# 26DC_20V_REBUILD.net
KiCad netlist of a schematic drawn in Altium Designer
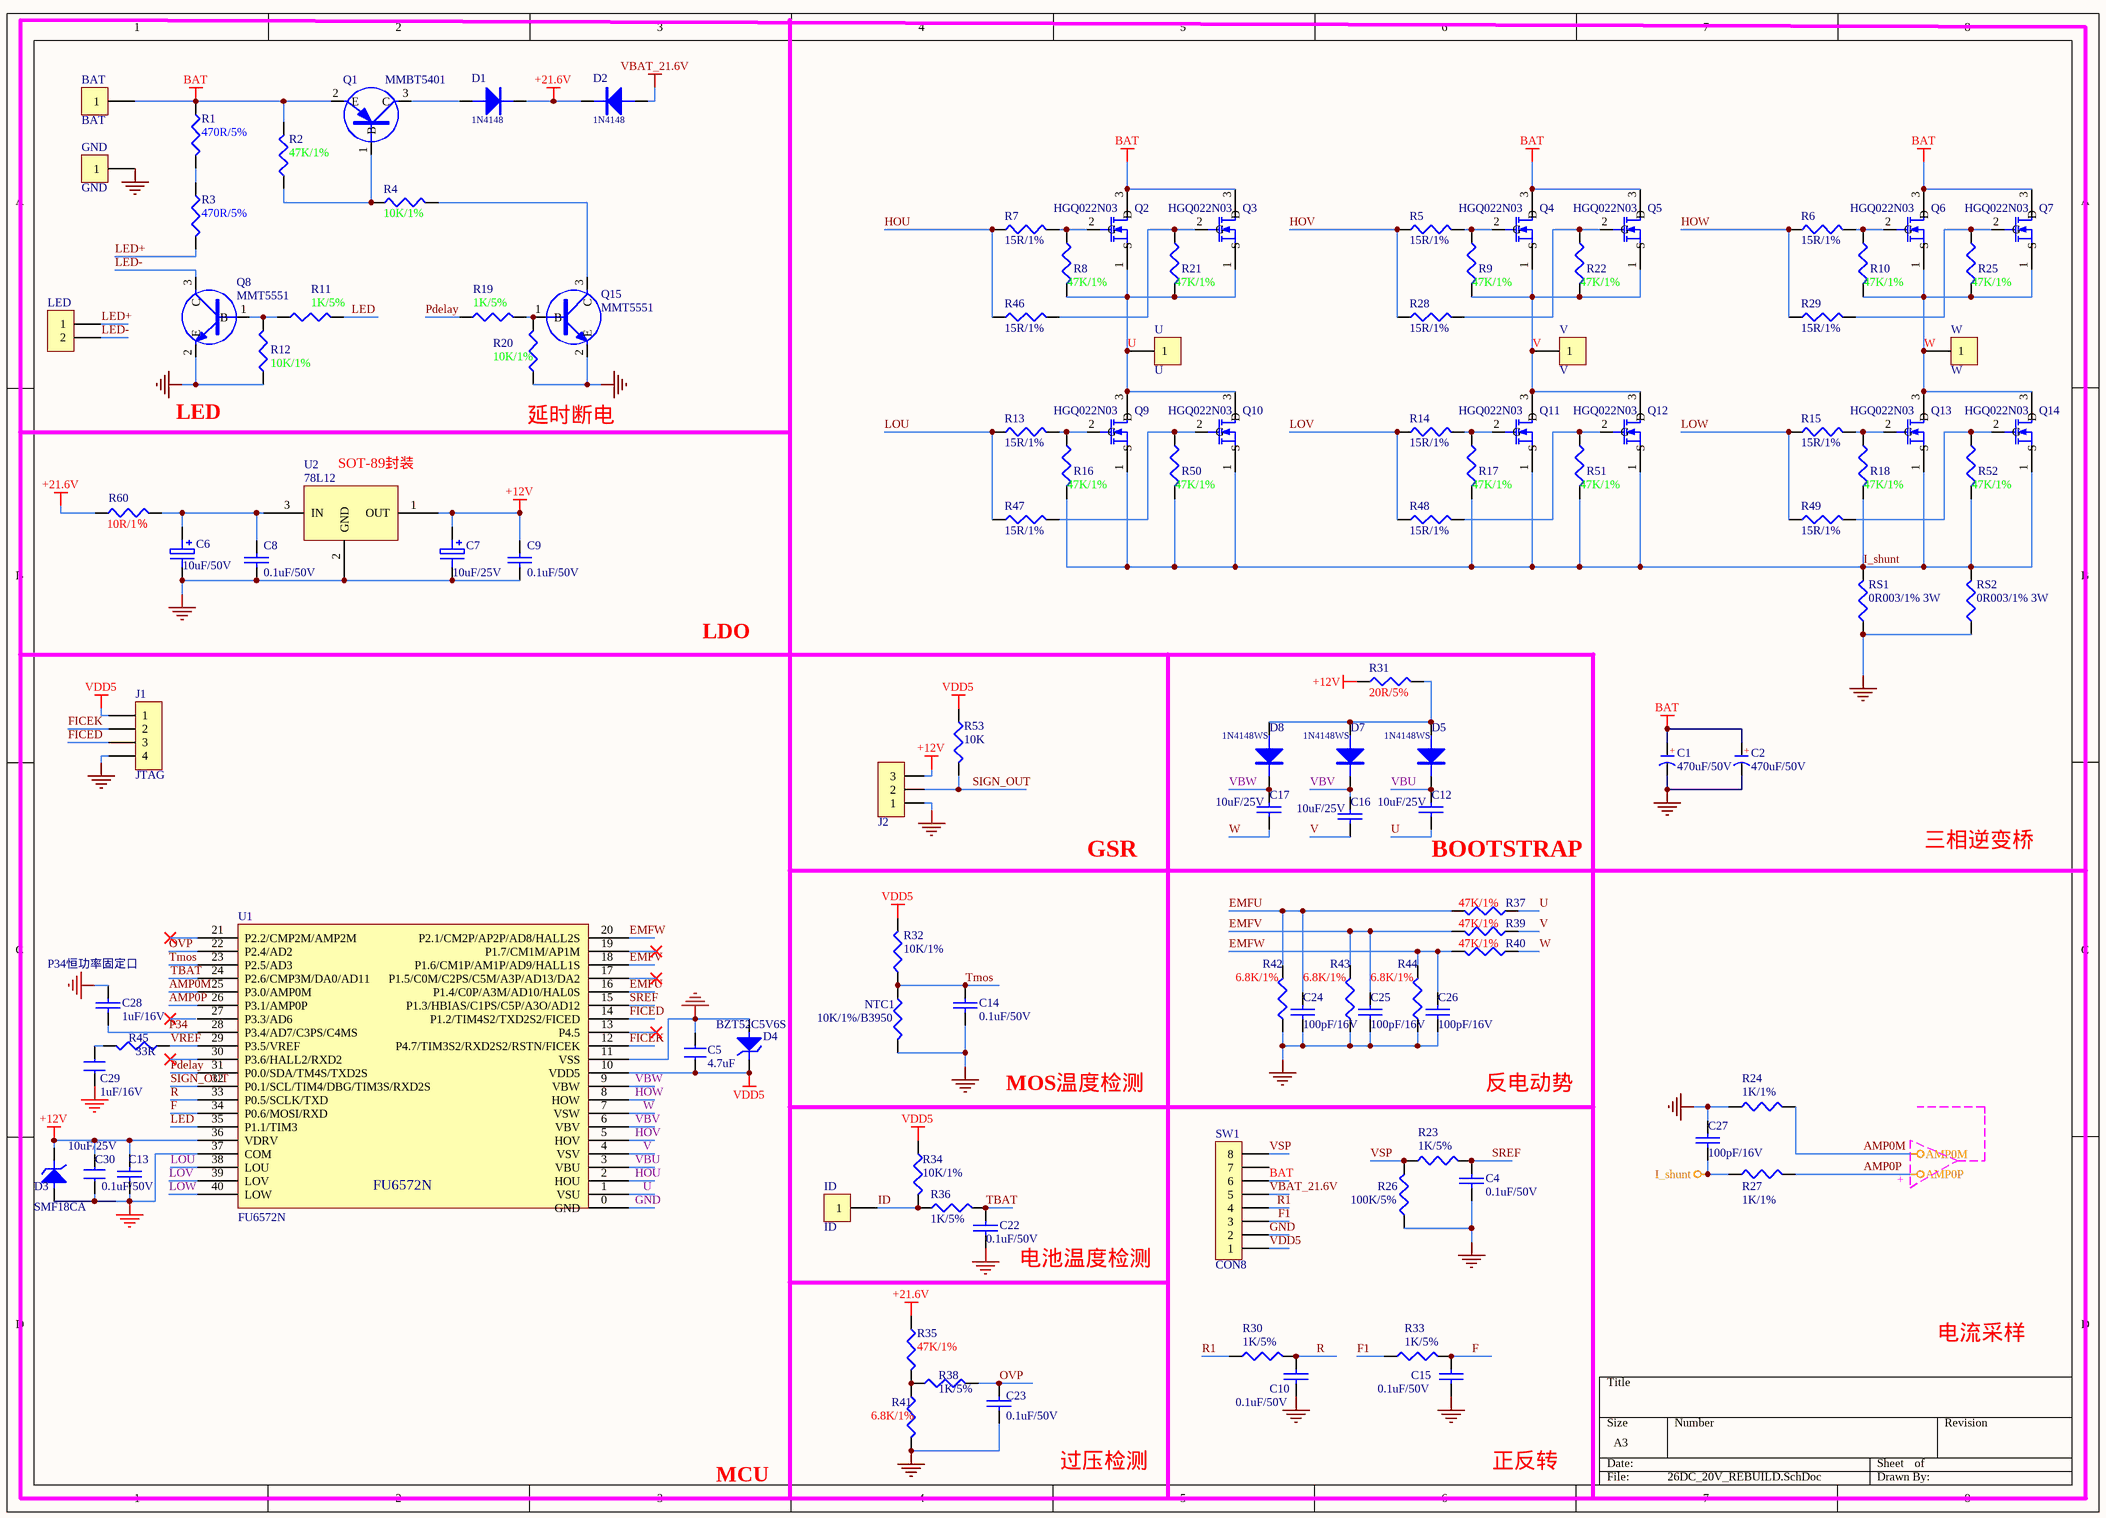
[diagram p0: 26DC_20V_REBUILD.SchDoc]

(export (version "E")
  (design (tool "Eeschema 10.0.6"))
  (components
    (comp (ref "BAT")
      (value "BAT")
      (footprint "TP")
      (description "Connector")
      (libsource (lib "26DC_20V_V1.3") (part "CON1_4"))
    )
    (comp (ref "C1")
      (value "470uF/50V")
      (footprint "CE-5.0*10*16 - GD")
      (description "直插电解电容")
      (libsource (lib "26DC_20V_V1.3") (part "CE"))
    )
    (comp (ref "C2")
      (value "470uF/50V")
      (footprint "CE-5.0*10*16 - GD")
      (description "直插电解电容")
      (libsource (lib "26DC_20V_V1.3") (part "CE"))
    )
    (comp (ref "C4")
      (value "0.1uF/50V")
      (footprint "C0603")
      (description "Capacitor")
      (libsource (lib "26DC_20V_V1.3") (part "CAP-CC"))
    )
    (comp (ref "C5")
      (value "4.7uF")
      (footprint "C0603")
      (description "Capacitor")
      (libsource (lib "") (part "CAP_1"))
    )
    (comp (ref "C6")
      (value "10uF/50V")
      (footprint "C0805")
      (description "Electrolytic Capacitor")
      (libsource (lib "26DC_20V_V1.3") (part "ELECTRO1"))
    )
    (comp (ref "C7")
      (value "10uF/25V")
      (footprint "C0805")
      (description "Electrolytic Capacitor")
      (libsource (lib "26DC_20V_V1.3") (part "ELECTRO1_1"))
    )
    (comp (ref "C8")
      (value "0.1uF/50V")
      (footprint "C0603")
      (description "Capacitor")
      (libsource (lib "26DC_20V_V1.3") (part "CAP"))
    )
    (comp (ref "C9")
      (value "0.1uF/50V")
      (footprint "C0603")
      (description "Capacitor")
      (libsource (lib "26DC_20V_V1.3") (part "CAP"))
    )
    (comp (ref "C10")
      (value "0.1uF/50V")
      (footprint "C0603")
      (description "Capacitor")
      (libsource (lib "26DC_20V_V1.3") (part "CAP-CC"))
    )
    (comp (ref "C12")
      (value "10uF/25V")
      (footprint "C0805")
      (description "Capacitor")
      (libsource (lib "*") (part "CAP-CC(SMD)"))
    )
    (comp (ref "C13")
      (value "0.1uF/50V")
      (footprint "C0603")
      (description "Capacitor")
      (libsource (lib "*") (part "CAP-CC"))
    )
    (comp (ref "C14")
      (value "0.1uF/50V")
      (footprint "C0603")
      (description "Capacitor")
      (libsource (lib "26DC_20V_V1.3") (part "CAP-CC"))
    )
    (comp (ref "C15")
      (value "0.1uF/50V")
      (footprint "C0603")
      (description "Capacitor")
      (libsource (lib "26DC_20V_V1.3") (part "CAP-CC"))
    )
    (comp (ref "C16")
      (value "10uF/25V")
      (footprint "C0805")
      (description "Capacitor")
      (libsource (lib "*") (part "CAP-CC(SMD)"))
    )
    (comp (ref "C17")
      (value "10uF/25V")
      (footprint "C0805")
      (description "Capacitor")
      (libsource (lib "*") (part "CAP-CC(SMD)"))
    )
    (comp (ref "C22")
      (value "0.1uF/50V")
      (footprint "C0603")
      (description "Capacitor")
      (libsource (lib "*") (part "CAP-CC"))
    )
    (comp (ref "C23")
      (value "0.1uF/50V")
      (footprint "C0603")
      (description "Capacitor")
      (libsource (lib "*") (part "CAP-CC"))
    )
    (comp (ref "C24")
      (value "100pF/16V")
      (footprint "C0603")
      (description "Capacitor")
      (libsource (lib "26DC_20V_V1.3") (part "CAP_1"))
    )
    (comp (ref "C25")
      (value "100pF/16V")
      (footprint "C0603")
      (description "Capacitor")
      (libsource (lib "26DC_20V_V1.3") (part "CAP_1"))
    )
    (comp (ref "C26")
      (value "100pF/16V")
      (footprint "C0603")
      (description "Capacitor")
      (libsource (lib "26DC_20V_V1.3") (part "CAP_1"))
    )
    (comp (ref "C27")
      (value "100pF/16V")
      (footprint "C0603")
      (description "Capacitor")
      (libsource (lib "26DC_20V_V1.3") (part "CAP_1"))
    )
    (comp (ref "C28")
      (value "1uF/16V")
      (footprint "C0603")
      (description "Capacitor")
      (libsource (lib "*") (part "CAP"))
    )
    (comp (ref "C29")
      (value "1uF/16V")
      (footprint "C0603")
      (description "Capacitor")
      (libsource (lib "") (part "CAP_1"))
    )
    (comp (ref "C30")
      (value "10uF/25V")
      (footprint "C0805")
      (description "Capacitor")
      (libsource (lib "") (part "CAP_1"))
    )
    (comp (ref "D1") (value "1N4148") (footprint "SOD-123") (libsource (lib "26DC_20V_V1.3") (part "DIODE")))
    (comp (ref "D2") (value "1N4148") (footprint "SOD-123") (libsource (lib "26DC_20V_V1.3") (part "DIODE")))
    (comp (ref "D3")
      (value "SMF18CA")
      (footprint "SOD-123")
      (description "Zener Diode")
      (libsource (lib "*") (part "TVS1"))
    )
    (comp (ref "D4")
      (value "BZT52C5V6S")
      (footprint "SOD-323")
      (description "Zener Diode")
      (libsource (lib "*") (part "TVS1"))
    )
    (comp (ref "D5")
      (value "1N4148WS")
      (footprint "SOD-323")
      (libsource (lib "FU6572N-HY-DC_V3.0") (part "DIODE"))
    )
    (comp (ref "D7")
      (value "1N4148WS")
      (footprint "SOD-323")
      (libsource (lib "FU6572N-HY-DC_V3.0") (part "DIODE"))
    )
    (comp (ref "D8")
      (value "1N4148WS")
      (footprint "SOD-323")
      (libsource (lib "FU6572N-HY-DC_V3.0") (part "DIODE"))
    )
    (comp (ref "GND")
      (value "GND")
      (footprint "TP")
      (description "Connector")
      (libsource (lib "26DC_20V_V1.3") (part "CON1_5"))
    )
    (comp (ref "ID")
      (value "ID")
      (footprint "TP")
      (description "Connector")
      (libsource (lib "*") (part "CON1"))
    )
    (comp (ref "J1")
      (value "JTAG")
      (footprint "4p-2.54-Pad")
      (description "Connector")
      (libsource (lib "26DC_20V_V1.3") (part "CON4"))
    )
    (comp (ref "J2")
      (value "HDR-1X3_1.25")
      (footprint "CONN-SMD-3P-P1.00_BM03B-SRSS-TB-LF-SN")
      (description "3P接插件_1.25")
      (libsource (lib "26DC_20V_V1.1") (part "Header 3_1.25"))
    )
    (comp (ref "LED")
      (value "CONN-SMD_2P-P1.00_HC-1.0-2PLT")
      (footprint "SMD_1.0_2P")
      (description "Connector")
      (libsource (lib "26DC_20V_V1.3") (part "CON2"))
    )
    (comp (ref "NTC1")
      (value "10K/1%/B3950")
      (footprint "R0603")
      (libsource (lib "26DC_20V_V1.3") (part "RES(SMD)_5"))
    )
    (comp (ref "Q1") (value "MMBT5401") (footprint "SOT-23") (libsource (lib "26DC_20V_V1.3") (part "PNP")))
    (comp (ref "Q2")
      (value "HGQ022N03")
      (footprint "DFN5*6")
      (libsource (lib "26DC_20V_V1.3") (part "HGQ022N03"))
    )
    (comp (ref "Q3")
      (value "HGQ022N03")
      (footprint "DFN5*6")
      (libsource (lib "26DC_20V_V1.3") (part "HGQ022N03"))
    )
    (comp (ref "Q4")
      (value "HGQ022N03")
      (footprint "DFN5*6")
      (libsource (lib "26DC_20V_V1.3") (part "HGQ022N03"))
    )
    (comp (ref "Q5")
      (value "HGQ022N03")
      (footprint "DFN5*6")
      (libsource (lib "26DC_20V_V1.3") (part "HGQ022N03"))
    )
    (comp (ref "Q6")
      (value "HGQ022N03")
      (footprint "DFN5*6")
      (libsource (lib "26DC_20V_V1.3") (part "HGQ022N03"))
    )
    (comp (ref "Q7")
      (value "HGQ022N03")
      (footprint "DFN5*6")
      (libsource (lib "26DC_20V_V1.3") (part "HGQ022N03"))
    )
    (comp (ref "Q8")
      (value "MMT5551")
      (footprint "SOT-23")
      (description "NPN Transistor")
      (libsource (lib "26DC_20V_V1.3") (part "NPN"))
    )
    (comp (ref "Q9")
      (value "HGQ022N03")
      (footprint "DFN5*6")
      (libsource (lib "26DC_20V_V1.3") (part "HGQ022N03"))
    )
    (comp (ref "Q10")
      (value "HGQ022N03")
      (footprint "DFN5*6")
      (libsource (lib "26DC_20V_V1.3") (part "HGQ022N03"))
    )
    (comp (ref "Q11")
      (value "HGQ022N03")
      (footprint "DFN5*6")
      (libsource (lib "26DC_20V_V1.3") (part "HGQ022N03"))
    )
    (comp (ref "Q12")
      (value "HGQ022N03")
      (footprint "DFN5*6")
      (libsource (lib "26DC_20V_V1.3") (part "HGQ022N03"))
    )
    (comp (ref "Q13")
      (value "HGQ022N03")
      (footprint "DFN5*6")
      (libsource (lib "26DC_20V_V1.3") (part "HGQ022N03"))
    )
    (comp (ref "Q14")
      (value "HGQ022N03")
      (footprint "DFN5*6")
      (libsource (lib "26DC_20V_V1.3") (part "HGQ022N03"))
    )
    (comp (ref "Q15")
      (value "MMT5551")
      (footprint "SOT-23")
      (description "NPN Transistor")
      (libsource (lib "26DC_20V_V1.3") (part "NPN"))
    )
    (comp (ref "R1")
      (value "470R/5%")
      (footprint "R1206")
      (libsource (lib "26DC_20V_V1.3") (part "RES(SMD)_4"))
    )
    (comp (ref "R2") (value "47K/1%") (footprint "R0603") (libsource (lib "26DC_20V_V1.3") (part "RES(SMD)")))
    (comp (ref "R3")
      (value "470R/5%")
      (footprint "R1206")
      (libsource (lib "26DC_20V_V1.3") (part "RES(SMD)_4"))
    )
    (comp (ref "R4")
      (value "10K/1%")
      (footprint "R0603")
      (libsource (lib "26DC_20V_V1.3") (part "RES(SMD)_3"))
    )
    (comp (ref "R5")
      (value "15R/1%")
      (footprint "R0603")
      (libsource (lib "26DC_20V_V1.3") (part "RES(SMD)_7"))
    )
    (comp (ref "R6")
      (value "15R/1%")
      (footprint "R0603")
      (libsource (lib "26DC_20V_V1.3") (part "RES(SMD)_7"))
    )
    (comp (ref "R7")
      (value "15R/1%")
      (footprint "R0603")
      (libsource (lib "26DC_20V_V1.3") (part "RES(SMD)_7"))
    )
    (comp (ref "R8")
      (value "47K/1%")
      (footprint "R0603")
      (description "RES")
      (libsource (lib "26DC_20V_V1.3") (part "RES-SMD"))
    )
    (comp (ref "R9")
      (value "47K/1%")
      (footprint "R0603")
      (description "RES")
      (libsource (lib "26DC_20V_V1.3") (part "RES-SMD"))
    )
    (comp (ref "R10")
      (value "47K/1%")
      (footprint "R0603")
      (description "RES")
      (libsource (lib "26DC_20V_V1.3") (part "RES-SMD"))
    )
    (comp (ref "R11")
      (value "1K/5%")
      (footprint "R0603")
      (libsource (lib "26DC_20V_V1.3") (part "RES(SMD)_2"))
    )
    (comp (ref "R12")
      (value "10K/1%")
      (footprint "R0603")
      (libsource (lib "26DC_20V_V1.3") (part "RES(SMD)_3"))
    )
    (comp (ref "R13")
      (value "15R/1%")
      (footprint "R0603")
      (libsource (lib "26DC_20V_V1.3") (part "RES(SMD)_7"))
    )
    (comp (ref "R14")
      (value "15R/1%")
      (footprint "R0603")
      (libsource (lib "26DC_20V_V1.3") (part "RES(SMD)_7"))
    )
    (comp (ref "R15")
      (value "15R/1%")
      (footprint "R0603")
      (libsource (lib "26DC_20V_V1.3") (part "RES(SMD)_7"))
    )
    (comp (ref "R16")
      (value "47K/1%")
      (footprint "R0603")
      (description "RES")
      (libsource (lib "26DC_20V_V1.3") (part "RES-SMD"))
    )
    (comp (ref "R17")
      (value "47K/1%")
      (footprint "R0603")
      (description "RES")
      (libsource (lib "26DC_20V_V1.3") (part "RES-SMD"))
    )
    (comp (ref "R18")
      (value "47K/1%")
      (footprint "R0603")
      (description "RES")
      (libsource (lib "26DC_20V_V1.3") (part "RES-SMD"))
    )
    (comp (ref "R19")
      (value "1K/5%")
      (footprint "R0603")
      (libsource (lib "26DC_20V_V1.3") (part "RES(SMD)_2"))
    )
    (comp (ref "R20")
      (value "10K/1%")
      (footprint "R0603")
      (libsource (lib "26DC_20V_V1.3") (part "RES(SMD)_3"))
    )
    (comp (ref "R21")
      (value "47K/1%")
      (footprint "R0603")
      (description "RES")
      (libsource (lib "26DC_20V_V1.3") (part "RES-SMD"))
    )
    (comp (ref "R22")
      (value "47K/1%")
      (footprint "R0603")
      (description "RES")
      (libsource (lib "26DC_20V_V1.3") (part "RES-SMD"))
    )
    (comp (ref "R23")
      (value "1K/5%")
      (footprint "R0603")
      (libsource (lib "26DC_20V_V1.3") (part "RES(SMD)_2"))
    )
    (comp (ref "R24")
      (value "1K/1%")
      (footprint "R0603")
      (libsource (lib "26DC_20V_V1.3") (part "RES(SMD)_11"))
    )
    (comp (ref "R25")
      (value "47K/1%")
      (footprint "R0603")
      (description "RES")
      (libsource (lib "26DC_20V_V1.3") (part "RES-SMD"))
    )
    (comp (ref "R26")
      (value "100K/5%")
      (footprint "R0603")
      (libsource (lib "26DC_20V_V1.3") (part "RES(SMD)_8"))
    )
    (comp (ref "R27")
      (value "1K/1%")
      (footprint "R0603")
      (libsource (lib "26DC_20V_V1.3") (part "RES(SMD)_11"))
    )
    (comp (ref "R28")
      (value "15R/1%")
      (footprint "R0603")
      (libsource (lib "26DC_20V_V1.3") (part "RES(SMD)_7"))
    )
    (comp (ref "R29")
      (value "15R/1%")
      (footprint "R0603")
      (libsource (lib "26DC_20V_V1.3") (part "RES(SMD)_7"))
    )
    (comp (ref "R30")
      (value "1K/5%")
      (footprint "R0603")
      (libsource (lib "26DC_20V_V1.3") (part "RES(SMD)_2"))
    )
    (comp (ref "R31") (value "20R/5%") (footprint "R1206") (libsource (lib "") (part "RES(SMD)_1")))
    (comp (ref "R32")
      (value "10K/1%")
      (footprint "R0603")
      (libsource (lib "26DC_20V_V1.3") (part "RES(SMD)_3"))
    )
    (comp (ref "R33")
      (value "1K/5%")
      (footprint "R0603")
      (libsource (lib "26DC_20V_V1.3") (part "RES(SMD)_2"))
    )
    (comp (ref "R34") (value "10K/1%") (footprint "R0603") (libsource (lib "*") (part "RES(SMD)")))
    (comp (ref "R35")
      (value "47K/1%")
      (footprint "R0603")
      (libsource (lib "26DC_20V_V1.3") (part "RES(SMD)"))
    )
    (comp (ref "R36") (value "1K/5%") (footprint "R0603") (libsource (lib "*") (part "RES(SMD)")))
    (comp (ref "R37")
      (value "47K/1%")
      (footprint "R0603")
      (libsource (lib "26DC_20V_V1.3") (part "RES(SMD)"))
    )
    (comp (ref "R38") (value "1K/5%") (footprint "R0603") (libsource (lib "*") (part "RES(SMD)")))
    (comp (ref "R39")
      (value "47K/1%")
      (footprint "R0603")
      (libsource (lib "26DC_20V_V1.3") (part "RES(SMD)"))
    )
    (comp (ref "R40")
      (value "47K/1%")
      (footprint "R0603")
      (libsource (lib "26DC_20V_V1.3") (part "RES(SMD)"))
    )
    (comp (ref "R41")
      (value "6.8K/1%")
      (footprint "R0603")
      (libsource (lib "26DC_20V_V1.3") (part "RES(SMD)"))
    )
    (comp (ref "R42")
      (value "6.8K/1%")
      (footprint "R0603")
      (libsource (lib "26DC_20V_V1.3") (part "RES(SMD)"))
    )
    (comp (ref "R43")
      (value "6.8K/1%")
      (footprint "R0603")
      (libsource (lib "26DC_20V_V1.3") (part "RES(SMD)"))
    )
    (comp (ref "R44")
      (value "6.8K/1%")
      (footprint "R0603")
      (libsource (lib "26DC_20V_V1.3") (part "RES(SMD)"))
    )
    (comp (ref "R45") (value "33R") (footprint "R0603") (libsource (lib "*") (part "RES(SMD)")))
    (comp (ref "R46")
      (value "15R/1%")
      (footprint "R0603")
      (libsource (lib "26DC_20V_V1.3") (part "RES(SMD)_7"))
    )
    (comp (ref "R47")
      (value "15R/1%")
      (footprint "R0603")
      (libsource (lib "26DC_20V_V1.3") (part "RES(SMD)_7"))
    )
    (comp (ref "R48")
      (value "15R/1%")
      (footprint "R0603")
      (libsource (lib "26DC_20V_V1.3") (part "RES(SMD)_7"))
    )
    (comp (ref "R49")
      (value "15R/1%")
      (footprint "R0603")
      (libsource (lib "26DC_20V_V1.3") (part "RES(SMD)_7"))
    )
    (comp (ref "R50")
      (value "47K/1%")
      (footprint "R0603")
      (description "RES")
      (libsource (lib "26DC_20V_V1.3") (part "RES-SMD"))
    )
    (comp (ref "R51")
      (value "47K/1%")
      (footprint "R0603")
      (description "RES")
      (libsource (lib "26DC_20V_V1.3") (part "RES-SMD"))
    )
    (comp (ref "R52")
      (value "47K/1%")
      (footprint "R0603")
      (description "RES")
      (libsource (lib "26DC_20V_V1.3") (part "RES-SMD"))
    )
    (comp (ref "R53") (value "10K") (footprint "R0603") (libsource (lib "*") (part "RES(SMD)")))
    (comp (ref "R60")
      (value "10R/1％")
      (footprint "R1206")
      (libsource (lib "26DC_20V_V1.3") (part "RES(SMD)_9"))
    )
    (comp (ref "RS1")
      (value "0R003/1% 3W")
      (footprint "R2512")
      (libsource (lib "26DC_20V_V1.3") (part "RES(SMD)_6"))
    )
    (comp (ref "RS2")
      (value "0R003/1% 3W")
      (footprint "R2512")
      (libsource (lib "26DC_20V_V1.3") (part "RES(SMD)_6"))
    )
    (comp (ref "SW1")
      (value "CON8")
      (footprint "CONN-SMD_8P-P1.00_MEGASTAR_ZX-SH1.0-8PLT")
      (description "Connector")
      (libsource (lib "26DC_20V_V1.3") (part "CON6"))
    )
    (comp (ref "U")
      (value "U")
      (footprint "TP")
      (description "Connector")
      (libsource (lib "26DC_20V_V1.3") (part "CON1"))
    )
    (comp (ref "U1") (value "FU6572N") (footprint "QFN40_5*5") (libsource (lib "SCH 常用封装") (part "FU6572N")))
    (comp (ref "U2")
      (value "78L12")
      (footprint "SOT-89")
      (libsource (lib "26DC_20V_V1.3") (part "78L12-12V"))
    )
    (comp (ref "V")
      (value "V")
      (footprint "TP")
      (description "Connector")
      (libsource (lib "26DC_20V_V1.3") (part "CON1"))
    )
    (comp (ref "W")
      (value "W")
      (footprint "TP")
      (description "Connector")
      (libsource (lib "26DC_20V_V1.3") (part "CON1"))
    )
  )
  (nets
    (net (code "1") (name "+12V") (class "Default")
      (node (ref "C13") (pin "1") (pinfunction "1_1") (pintype "passive"))
      (node (ref "C30") (pin "2") (pinfunction "2_2") (pintype "passive"))
      (node (ref "C7") (pin "1") (pinfunction "1_1") (pintype "passive"))
      (node (ref "C9") (pin "1") (pinfunction "1_1") (pintype "passive"))
      (node (ref "D3") (pin "2") (pinfunction "K_2") (pintype "passive"))
      (node (ref "J2") (pin "3") (pinfunction "3_3") (pintype "passive"))
      (node (ref "R31") (pin "1") (pinfunction "1_1") (pintype "passive"))
      (node (ref "U1") (pin "36") (pinfunction "VDRV_36") (pintype "passive"))
      (node (ref "U2") (pin "1") (pinfunction "OUT_1") (pintype "passive"))
    )
    (net (code "2") (name "+21.6V") (class "Default")
      (node (ref "D1") (pin "K") (pinfunction "K_K") (pintype "passive"))
      (node (ref "D2") (pin "K") (pinfunction "K_K") (pintype "passive"))
      (node (ref "R35") (pin "1") (pinfunction "1_1") (pintype "passive"))
      (node (ref "R60") (pin "1") (pinfunction "1_1") (pintype "passive"))
    )
    (net (code "3") (name "/EMFU") (class "Default")
      (node (ref "C24") (pin "2") (pinfunction "2_2") (pintype "passive"))
      (node (ref "R37") (pin "2") (pinfunction "2_2") (pintype "passive"))
      (node (ref "R42") (pin "2") (pinfunction "2_2") (pintype "passive"))
      (node (ref "U1") (pin "16") (pinfunction "P1.4/C0P/A3M/AD10/HAL0S_16") (pintype "passive"))
    )
    (net (code "4") (name "/EMFV") (class "Default")
      (node (ref "C25") (pin "2") (pinfunction "2_2") (pintype "passive"))
      (node (ref "R39") (pin "2") (pinfunction "2_2") (pintype "passive"))
      (node (ref "R43") (pin "2") (pinfunction "2_2") (pintype "passive"))
      (node (ref "U1") (pin "18") (pinfunction "P1.6/CM1P/AM1P/AD9/HALL1S_18") (pintype "passive"))
    )
    (net (code "5") (name "/EMFW") (class "Default")
      (node (ref "C26") (pin "2") (pinfunction "2_2") (pintype "passive"))
      (node (ref "R40") (pin "2") (pinfunction "2_2") (pintype "passive"))
      (node (ref "R44") (pin "2") (pinfunction "2_2") (pintype "passive"))
      (node (ref "U1") (pin "20") (pinfunction "P2.1/CM2P/AP2P/AD8/HALL2S_20") (pintype "passive"))
    )
    (net (code "6") (name "/F") (class "Default")
      (node (ref "C15") (pin "1") (pinfunction "1_1") (pintype "passive"))
      (node (ref "R33") (pin "2") (pinfunction "2_2") (pintype "passive"))
      (node (ref "U1") (pin "34") (pinfunction "P0.6/MOSI/RXD_34") (pintype "passive"))
    )
    (net (code "7") (name "/F1") (class "Default")
      (node (ref "R33") (pin "1") (pinfunction "1_1") (pintype "passive"))
      (node (ref "SW1") (pin "3") (pinfunction "3_3") (pintype "passive"))
    )
    (net (code "8") (name "/FICED") (class "Default")
      (node (ref "J1") (pin "3") (pinfunction "3_3") (pintype "passive"))
      (node (ref "U1") (pin "14") (pinfunction "P1.2/TIM4S2/TXD2S2/FICED_14") (pintype "passive"))
    )
    (net (code "9") (name "/FICEK") (class "Default")
      (node (ref "J1") (pin "2") (pinfunction "2_2") (pintype "passive"))
      (node (ref "U1") (pin "12") (pinfunction "P4.7/TIM3S2/RXD2S2/RSTN/FICEK_12") (pintype "passive"))
    )
    (net (code "10") (name "/HOU") (class "Default")
      (node (ref "R46") (pin "1") (pinfunction "1_1") (pintype "passive"))
      (node (ref "R7") (pin "1") (pinfunction "1_1") (pintype "passive"))
      (node (ref "U1") (pin "2") (pinfunction "HOU_2") (pintype "passive"))
    )
    (net (code "11") (name "/HOV") (class "Default")
      (node (ref "R28") (pin "1") (pinfunction "1_1") (pintype "passive"))
      (node (ref "R5") (pin "1") (pinfunction "1_1") (pintype "passive"))
      (node (ref "U1") (pin "5") (pinfunction "HOV_5") (pintype "passive"))
    )
    (net (code "12") (name "/HOW") (class "Default")
      (node (ref "R29") (pin "1") (pinfunction "1_1") (pintype "passive"))
      (node (ref "R6") (pin "1") (pinfunction "1_1") (pintype "passive"))
      (node (ref "U1") (pin "8") (pinfunction "HOW_8") (pintype "passive"))
    )
    (net (code "13") (name "/ID") (class "Default")
      (node (ref "ID") (pin "1") (pinfunction "1_1") (pintype "passive"))
      (node (ref "R34") (pin "2") (pinfunction "2_2") (pintype "passive"))
      (node (ref "R36") (pin "1") (pinfunction "1_1") (pintype "passive"))
    )
    (net (code "14") (name "/LED") (class "Default")
      (node (ref "R11") (pin "2") (pinfunction "2_2") (pintype "passive"))
      (node (ref "U1") (pin "35") (pinfunction "P1.1/TIM3_35") (pintype "passive"))
    )
    (net (code "15") (name "/LED+") (class "Default")
      (node (ref "LED") (pin "1") (pinfunction "1_1") (pintype "passive"))
      (node (ref "R3") (pin "2") (pinfunction "2_2") (pintype "passive"))
    )
    (net (code "16") (name "/LED-") (class "Default")
      (node (ref "LED") (pin "2") (pinfunction "2_2") (pintype "passive"))
      (node (ref "Q8") (pin "3") (pinfunction "C_3") (pintype "passive"))
    )
    (net (code "17") (name "/LOU") (class "Default")
      (node (ref "R13") (pin "1") (pinfunction "1_1") (pintype "passive"))
      (node (ref "R47") (pin "1") (pinfunction "1_1") (pintype "passive"))
      (node (ref "U1") (pin "38") (pinfunction "LOU_38") (pintype "passive"))
    )
    (net (code "18") (name "/LOV") (class "Default")
      (node (ref "R14") (pin "1") (pinfunction "1_1") (pintype "passive"))
      (node (ref "R48") (pin "1") (pinfunction "1_1") (pintype "passive"))
      (node (ref "U1") (pin "39") (pinfunction "LOV_39") (pintype "passive"))
    )
    (net (code "19") (name "/LOW") (class "Default")
      (node (ref "R15") (pin "1") (pinfunction "1_1") (pintype "passive"))
      (node (ref "R49") (pin "1") (pinfunction "1_1") (pintype "passive"))
      (node (ref "U1") (pin "40") (pinfunction "LOW_40") (pintype "passive"))
    )
    (net (code "20") (name "/OVP") (class "Default")
      (node (ref "C23") (pin "1") (pinfunction "1_1") (pintype "passive"))
      (node (ref "R38") (pin "2") (pinfunction "2_2") (pintype "passive"))
      (node (ref "U1") (pin "22") (pinfunction "P2.4/AD2_22") (pintype "passive"))
    )
    (net (code "21") (name "/P34") (class "Default")
      (node (ref "C28") (pin "1") (pinfunction "1_1") (pintype "passive"))
      (node (ref "U1") (pin "28") (pinfunction "P3.4/AD7/C3PS/C4MS_28") (pintype "passive"))
    )
    (net (code "22") (name "/Pdelay") (class "Default")
      (node (ref "R19") (pin "1") (pinfunction "1_1") (pintype "passive"))
      (node (ref "U1") (pin "31") (pinfunction "P0.0/SDA/TM4S/TXD2S_31") (pintype "passive"))
    )
    (net (code "23") (name "/R") (class "Default")
      (node (ref "C10") (pin "1") (pinfunction "1_1") (pintype "passive"))
      (node (ref "R30") (pin "2") (pinfunction "2_2") (pintype "passive"))
      (node (ref "U1") (pin "33") (pinfunction "P0.5/SCLK/TXD_33") (pintype "passive"))
    )
    (net (code "24") (name "/R1") (class "Default")
      (node (ref "R30") (pin "1") (pinfunction "1_1") (pintype "passive"))
      (node (ref "SW1") (pin "4") (pinfunction "4_4") (pintype "passive"))
    )
    (net (code "25") (name "/SIGN_OUT") (class "Default")
      (node (ref "J2") (pin "2") (pinfunction "2_2") (pintype "passive"))
      (node (ref "R53") (pin "2") (pinfunction "2_2") (pintype "passive"))
      (node (ref "U1") (pin "32") (pinfunction "P0.1/SCL/TIM4/DBG/TIM3S/RXD2S_32") (pintype "passive"))
    )
    (net (code "26") (name "/SREF") (class "Default")
      (node (ref "C4") (pin "1") (pinfunction "1_1") (pintype "passive"))
      (node (ref "R23") (pin "2") (pinfunction "2_2") (pintype "passive"))
      (node (ref "U1") (pin "15") (pinfunction "P1.3/HBIAS/C1PS/C5P/A3O/AD12_15") (pintype "passive"))
    )
    (net (code "27") (name "/TBAT") (class "Default")
      (node (ref "C22") (pin "1") (pinfunction "1_1") (pintype "passive"))
      (node (ref "R36") (pin "2") (pinfunction "2_2") (pintype "passive"))
      (node (ref "U1") (pin "24") (pinfunction "P2.6/CMP3M/DA0/AD11_24") (pintype "passive"))
    )
    (net (code "28") (name "/Tmos") (class "Default")
      (node (ref "C14") (pin "1") (pinfunction "1_1") (pintype "passive"))
      (node (ref "NTC1") (pin "1") (pinfunction "1_1") (pintype "passive"))
      (node (ref "R32") (pin "1") (pinfunction "1_1") (pintype "passive"))
      (node (ref "U1") (pin "23") (pinfunction "P2.5/AD3_23") (pintype "passive"))
    )
    (net (code "29") (name "/U") (class "Default")
      (node (ref "C12") (pin "2") (pinfunction "2_2") (pintype "passive"))
      (node (ref "Q10") (pin "3") (pinfunction "D_3") (pintype "passive"))
      (node (ref "Q2") (pin "1") (pinfunction "S_1") (pintype "passive"))
      (node (ref "Q3") (pin "1") (pinfunction "S_1") (pintype "passive"))
      (node (ref "Q9") (pin "3") (pinfunction "D_3") (pintype "passive"))
      (node (ref "R21") (pin "2") (pinfunction "2_2") (pintype "passive"))
      (node (ref "R37") (pin "1") (pinfunction "1_1") (pintype "passive"))
      (node (ref "R8") (pin "2") (pinfunction "2_2") (pintype "passive"))
      (node (ref "U") (pin "1") (pinfunction "1_1") (pintype "passive"))
      (node (ref "U1") (pin "1") (pinfunction "VSU_1") (pintype "passive"))
    )
    (net (code "30") (name "/V") (class "Default")
      (node (ref "C16") (pin "1") (pinfunction "1_1") (pintype "passive"))
      (node (ref "Q11") (pin "3") (pinfunction "D_3") (pintype "passive"))
      (node (ref "Q12") (pin "3") (pinfunction "D_3") (pintype "passive"))
      (node (ref "Q4") (pin "1") (pinfunction "S_1") (pintype "passive"))
      (node (ref "Q5") (pin "1") (pinfunction "S_1") (pintype "passive"))
      (node (ref "R22") (pin "2") (pinfunction "2_2") (pintype "passive"))
      (node (ref "R39") (pin "1") (pinfunction "1_1") (pintype "passive"))
      (node (ref "R9") (pin "2") (pinfunction "2_2") (pintype "passive"))
      (node (ref "U1") (pin "4") (pinfunction "VSV_4") (pintype "passive"))
      (node (ref "V") (pin "1") (pinfunction "1_1") (pintype "passive"))
    )
    (net (code "31") (name "/VBU") (class "Default")
      (node (ref "C12") (pin "1") (pinfunction "1_1") (pintype "passive"))
      (node (ref "D5") (pin "K") (pinfunction "K_K") (pintype "passive"))
      (node (ref "U1") (pin "3") (pinfunction "VBU_3") (pintype "passive"))
    )
    (net (code "32") (name "/VBV") (class "Default")
      (node (ref "C16") (pin "2") (pinfunction "2_2") (pintype "passive"))
      (node (ref "D7") (pin "K") (pinfunction "K_K") (pintype "passive"))
      (node (ref "U1") (pin "6") (pinfunction "VBV_6") (pintype "passive"))
    )
    (net (code "33") (name "/VBW") (class "Default")
      (node (ref "C17") (pin "1") (pinfunction "1_1") (pintype "passive"))
      (node (ref "D8") (pin "K") (pinfunction "K_K") (pintype "passive"))
      (node (ref "U1") (pin "9") (pinfunction "VBW_9") (pintype "passive"))
    )
    (net (code "34") (name "/VREF") (class "Default")
      (node (ref "R45") (pin "1") (pinfunction "1_1") (pintype "passive"))
      (node (ref "U1") (pin "29") (pinfunction "P3.5/VREF_29") (pintype "passive"))
    )
    (net (code "35") (name "/VSP") (class "Default")
      (node (ref "R23") (pin "1") (pinfunction "1_1") (pintype "passive"))
      (node (ref "R26") (pin "2") (pinfunction "2_2") (pintype "passive"))
      (node (ref "SW1") (pin "8") (pinfunction "8_8") (pintype "passive"))
    )
    (net (code "36") (name "/W") (class "Default")
      (node (ref "C17") (pin "2") (pinfunction "2_2") (pintype "passive"))
      (node (ref "Q13") (pin "3") (pinfunction "D_3") (pintype "passive"))
      (node (ref "Q14") (pin "3") (pinfunction "D_3") (pintype "passive"))
      (node (ref "Q6") (pin "1") (pinfunction "S_1") (pintype "passive"))
      (node (ref "Q7") (pin "1") (pinfunction "S_1") (pintype "passive"))
      (node (ref "R10") (pin "2") (pinfunction "2_2") (pintype "passive"))
      (node (ref "R25") (pin "2") (pinfunction "2_2") (pintype "passive"))
      (node (ref "R40") (pin "1") (pinfunction "1_1") (pintype "passive"))
      (node (ref "U1") (pin "7") (pinfunction "VSW_7") (pintype "passive"))
      (node (ref "W") (pin "1") (pinfunction "1_1") (pintype "passive"))
    )
    (net (code "37") (name "AMP0M") (class "Default")
      (node (ref "R24") (pin "2") (pinfunction "2_2") (pintype "passive"))
      (node (ref "U1") (pin "25") (pinfunction "P3.0/AMP0M_25") (pintype "passive"))
    )
    (net (code "38") (name "AMP0P") (class "Default")
      (node (ref "R27") (pin "2") (pinfunction "2_2") (pintype "passive"))
      (node (ref "U1") (pin "26") (pinfunction "P3.1/AMP0P_26") (pintype "passive"))
    )
    (net (code "39") (name "BAT") (class "Default")
      (node (ref "BAT") (pin "1") (pinfunction "1_1") (pintype "passive"))
      (node (ref "C1") (pin "1") (pinfunction "A_1") (pintype "passive"))
      (node (ref "C2") (pin "1") (pinfunction "A_1") (pintype "passive"))
      (node (ref "Q1") (pin "2") (pinfunction "E_2") (pintype "passive"))
      (node (ref "Q2") (pin "3") (pinfunction "D_3") (pintype "passive"))
      (node (ref "Q3") (pin "3") (pinfunction "D_3") (pintype "passive"))
      (node (ref "Q4") (pin "3") (pinfunction "D_3") (pintype "passive"))
      (node (ref "Q5") (pin "3") (pinfunction "D_3") (pintype "passive"))
      (node (ref "Q6") (pin "3") (pinfunction "D_3") (pintype "passive"))
      (node (ref "Q7") (pin "3") (pinfunction "D_3") (pintype "passive"))
      (node (ref "R1") (pin "1") (pinfunction "1_1") (pintype "passive"))
      (node (ref "R2") (pin "2") (pinfunction "2_2") (pintype "passive"))
      (node (ref "SW1") (pin "6") (pinfunction "6_6") (pintype "passive"))
    )
    (net (code "40") (name "GND") (class "Default")
      (node (ref "C1") (pin "2") (pinfunction "K_2") (pintype "passive"))
      (node (ref "C10") (pin "2") (pinfunction "2_2") (pintype "passive"))
      (node (ref "C13") (pin "2") (pinfunction "2_2") (pintype "passive"))
      (node (ref "C14") (pin "2") (pinfunction "2_2") (pintype "passive"))
      (node (ref "C15") (pin "2") (pinfunction "2_2") (pintype "passive"))
      (node (ref "C2") (pin "2") (pinfunction "K_2") (pintype "passive"))
      (node (ref "C22") (pin "2") (pinfunction "2_2") (pintype "passive"))
      (node (ref "C23") (pin "2") (pinfunction "2_2") (pintype "passive"))
      (node (ref "C24") (pin "1") (pinfunction "1_1") (pintype "passive"))
      (node (ref "C25") (pin "1") (pinfunction "1_1") (pintype "passive"))
      (node (ref "C26") (pin "1") (pinfunction "1_1") (pintype "passive"))
      (node (ref "C27") (pin "1") (pinfunction "1_1") (pintype "passive"))
      (node (ref "C28") (pin "2") (pinfunction "2_2") (pintype "passive"))
      (node (ref "C29") (pin "1") (pinfunction "1_1") (pintype "passive"))
      (node (ref "C30") (pin "1") (pinfunction "1_1") (pintype "passive"))
      (node (ref "C4") (pin "2") (pinfunction "2_2") (pintype "passive"))
      (node (ref "C5") (pin "2") (pinfunction "2_2") (pintype "passive"))
      (node (ref "C6") (pin "2") (pinfunction "2_2") (pintype "passive"))
      (node (ref "C7") (pin "2") (pinfunction "2_2") (pintype "passive"))
      (node (ref "C8") (pin "2") (pinfunction "2_2") (pintype "passive"))
      (node (ref "C9") (pin "2") (pinfunction "2_2") (pintype "passive"))
      (node (ref "D3") (pin "1") (pinfunction "A_1") (pintype "passive"))
      (node (ref "D4") (pin "1") (pinfunction "A_1") (pintype "passive"))
      (node (ref "GND") (pin "1") (pinfunction "1_1") (pintype "passive"))
      (node (ref "J1") (pin "4") (pinfunction "4_4") (pintype "passive"))
      (node (ref "J2") (pin "1") (pinfunction "1_1") (pintype "passive"))
      (node (ref "NTC1") (pin "2") (pinfunction "2_2") (pintype "passive"))
      (node (ref "Q15") (pin "2") (pinfunction "E_2") (pintype "passive"))
      (node (ref "Q8") (pin "2") (pinfunction "E_2") (pintype "passive"))
      (node (ref "R12") (pin "1") (pinfunction "1_1") (pintype "passive"))
      (node (ref "R20") (pin "1") (pinfunction "1_1") (pintype "passive"))
      (node (ref "R24") (pin "1") (pinfunction "1_1") (pintype "passive"))
      (node (ref "R26") (pin "1") (pinfunction "1_1") (pintype "passive"))
      (node (ref "R41") (pin "2") (pinfunction "2_2") (pintype "passive"))
      (node (ref "R42") (pin "1") (pinfunction "1_1") (pintype "passive"))
      (node (ref "R43") (pin "1") (pinfunction "1_1") (pintype "passive"))
      (node (ref "R44") (pin "1") (pinfunction "1_1") (pintype "passive"))
      (node (ref "RS1") (pin "1") (pinfunction "1_1") (pintype "passive"))
      (node (ref "RS2") (pin "1") (pinfunction "1_1") (pintype "passive"))
      (node (ref "SW1") (pin "2") (pinfunction "2_2") (pintype "passive"))
      (node (ref "U1") (pin "0") (pinfunction "GND_0") (pintype "passive"))
      (node (ref "U1") (pin "11") (pinfunction "VSS_11") (pintype "passive"))
      (node (ref "U1") (pin "37") (pinfunction "COM_37") (pintype "passive"))
      (node (ref "U2") (pin "2") (pinfunction "GND_2") (pintype "passive"))
    )
    (net (code "41") (name "I_shunt") (class "Default")
      (node (ref "C27") (pin "2") (pinfunction "2_2") (pintype "passive"))
      (node (ref "Q10") (pin "1") (pinfunction "S_1") (pintype "passive"))
      (node (ref "Q11") (pin "1") (pinfunction "S_1") (pintype "passive"))
      (node (ref "Q12") (pin "1") (pinfunction "S_1") (pintype "passive"))
      (node (ref "Q13") (pin "1") (pinfunction "S_1") (pintype "passive"))
      (node (ref "Q14") (pin "1") (pinfunction "S_1") (pintype "passive"))
      (node (ref "Q9") (pin "1") (pinfunction "S_1") (pintype "passive"))
      (node (ref "R16") (pin "2") (pinfunction "2_2") (pintype "passive"))
      (node (ref "R17") (pin "2") (pinfunction "2_2") (pintype "passive"))
      (node (ref "R18") (pin "2") (pinfunction "2_2") (pintype "passive"))
      (node (ref "R27") (pin "1") (pinfunction "1_1") (pintype "passive"))
      (node (ref "R50") (pin "2") (pinfunction "2_2") (pintype "passive"))
      (node (ref "R51") (pin "2") (pinfunction "2_2") (pintype "passive"))
      (node (ref "R52") (pin "2") (pinfunction "2_2") (pintype "passive"))
      (node (ref "RS1") (pin "2") (pinfunction "2_2") (pintype "passive"))
      (node (ref "RS2") (pin "2") (pinfunction "2_2") (pintype "passive"))
    )
    (net (code "42") (name "Net-(C29-Pad2)") (class "Default")
      (node (ref "C29") (pin "2") (pinfunction "2_2") (pintype "passive"))
      (node (ref "R45") (pin "2") (pinfunction "2_2") (pintype "passive"))
    )
    (net (code "43") (name "Net-(D5-PadA)") (class "Default")
      (node (ref "D5") (pin "A") (pinfunction "A_A") (pintype "passive"))
      (node (ref "D7") (pin "A") (pinfunction "A_A") (pintype "passive"))
      (node (ref "D8") (pin "A") (pinfunction "A_A") (pintype "passive"))
      (node (ref "R31") (pin "2") (pinfunction "2_2") (pintype "passive"))
    )
    (net (code "44") (name "Net-(Q1-B)") (class "Default")
      (node (ref "Q1") (pin "1") (pinfunction "B_1") (pintype "passive"))
      (node (ref "R2") (pin "1") (pinfunction "1_1") (pintype "passive"))
      (node (ref "R4") (pin "1") (pinfunction "1_1") (pintype "passive"))
    )
    (net (code "45") (name "Net-(Q1-C)") (class "Default")
      (node (ref "D1") (pin "A") (pinfunction "A_A") (pintype "passive"))
      (node (ref "Q1") (pin "3") (pinfunction "C_3") (pintype "passive"))
    )
    (net (code "46") (name "Net-(Q2-G)") (class "Default")
      (node (ref "Q2") (pin "2") (pinfunction "G_2") (pintype "passive"))
      (node (ref "R7") (pin "2") (pinfunction "2_2") (pintype "passive"))
      (node (ref "R8") (pin "1") (pinfunction "1_1") (pintype "passive"))
    )
    (net (code "47") (name "Net-(Q3-G)") (class "Default")
      (node (ref "Q3") (pin "2") (pinfunction "G_2") (pintype "passive"))
      (node (ref "R21") (pin "1") (pinfunction "1_1") (pintype "passive"))
      (node (ref "R46") (pin "2") (pinfunction "2_2") (pintype "passive"))
    )
    (net (code "48") (name "Net-(Q4-G)") (class "Default")
      (node (ref "Q4") (pin "2") (pinfunction "G_2") (pintype "passive"))
      (node (ref "R5") (pin "2") (pinfunction "2_2") (pintype "passive"))
      (node (ref "R9") (pin "1") (pinfunction "1_1") (pintype "passive"))
    )
    (net (code "49") (name "Net-(Q5-G)") (class "Default")
      (node (ref "Q5") (pin "2") (pinfunction "G_2") (pintype "passive"))
      (node (ref "R22") (pin "1") (pinfunction "1_1") (pintype "passive"))
      (node (ref "R28") (pin "2") (pinfunction "2_2") (pintype "passive"))
    )
    (net (code "50") (name "Net-(Q6-G)") (class "Default")
      (node (ref "Q6") (pin "2") (pinfunction "G_2") (pintype "passive"))
      (node (ref "R10") (pin "1") (pinfunction "1_1") (pintype "passive"))
      (node (ref "R6") (pin "2") (pinfunction "2_2") (pintype "passive"))
    )
    (net (code "51") (name "Net-(Q7-G)") (class "Default")
      (node (ref "Q7") (pin "2") (pinfunction "G_2") (pintype "passive"))
      (node (ref "R25") (pin "1") (pinfunction "1_1") (pintype "passive"))
      (node (ref "R29") (pin "2") (pinfunction "2_2") (pintype "passive"))
    )
    (net (code "52") (name "Net-(Q8-B)") (class "Default")
      (node (ref "Q8") (pin "1") (pinfunction "B_1") (pintype "passive"))
      (node (ref "R11") (pin "1") (pinfunction "1_1") (pintype "passive"))
      (node (ref "R12") (pin "2") (pinfunction "2_2") (pintype "passive"))
    )
    (net (code "53") (name "Net-(Q9-G)") (class "Default")
      (node (ref "Q9") (pin "2") (pinfunction "G_2") (pintype "passive"))
      (node (ref "R13") (pin "2") (pinfunction "2_2") (pintype "passive"))
      (node (ref "R16") (pin "1") (pinfunction "1_1") (pintype "passive"))
    )
    (net (code "54") (name "Net-(Q10-G)") (class "Default")
      (node (ref "Q10") (pin "2") (pinfunction "G_2") (pintype "passive"))
      (node (ref "R47") (pin "2") (pinfunction "2_2") (pintype "passive"))
      (node (ref "R50") (pin "1") (pinfunction "1_1") (pintype "passive"))
    )
    (net (code "55") (name "Net-(Q11-G)") (class "Default")
      (node (ref "Q11") (pin "2") (pinfunction "G_2") (pintype "passive"))
      (node (ref "R14") (pin "2") (pinfunction "2_2") (pintype "passive"))
      (node (ref "R17") (pin "1") (pinfunction "1_1") (pintype "passive"))
    )
    (net (code "56") (name "Net-(Q12-G)") (class "Default")
      (node (ref "Q12") (pin "2") (pinfunction "G_2") (pintype "passive"))
      (node (ref "R48") (pin "2") (pinfunction "2_2") (pintype "passive"))
      (node (ref "R51") (pin "1") (pinfunction "1_1") (pintype "passive"))
    )
    (net (code "57") (name "Net-(Q13-G)") (class "Default")
      (node (ref "Q13") (pin "2") (pinfunction "G_2") (pintype "passive"))
      (node (ref "R15") (pin "2") (pinfunction "2_2") (pintype "passive"))
      (node (ref "R18") (pin "1") (pinfunction "1_1") (pintype "passive"))
    )
    (net (code "58") (name "Net-(Q14-G)") (class "Default")
      (node (ref "Q14") (pin "2") (pinfunction "G_2") (pintype "passive"))
      (node (ref "R49") (pin "2") (pinfunction "2_2") (pintype "passive"))
      (node (ref "R52") (pin "1") (pinfunction "1_1") (pintype "passive"))
    )
    (net (code "59") (name "Net-(Q15-B)") (class "Default")
      (node (ref "Q15") (pin "1") (pinfunction "B_1") (pintype "passive"))
      (node (ref "R19") (pin "2") (pinfunction "2_2") (pintype "passive"))
      (node (ref "R20") (pin "2") (pinfunction "2_2") (pintype "passive"))
    )
    (net (code "60") (name "Net-(Q15-C)") (class "Default")
      (node (ref "Q15") (pin "3") (pinfunction "C_3") (pintype "passive"))
      (node (ref "R4") (pin "2") (pinfunction "2_2") (pintype "passive"))
    )
    (net (code "61") (name "Net-(R1-Pad2)") (class "Default")
      (node (ref "R1") (pin "2") (pinfunction "2_2") (pintype "passive"))
      (node (ref "R3") (pin "1") (pinfunction "1_1") (pintype "passive"))
    )
    (net (code "62") (name "Net-(R35-Pad2)") (class "Default")
      (node (ref "R35") (pin "2") (pinfunction "2_2") (pintype "passive"))
      (node (ref "R38") (pin "1") (pinfunction "1_1") (pintype "passive"))
      (node (ref "R41") (pin "1") (pinfunction "1_1") (pintype "passive"))
    )
    (net (code "63") (name "Net-(U2-IN)") (class "Default")
      (node (ref "C6") (pin "1") (pinfunction "1_1") (pintype "passive"))
      (node (ref "C8") (pin "1") (pinfunction "1_1") (pintype "passive"))
      (node (ref "R60") (pin "2") (pinfunction "2_2") (pintype "passive"))
      (node (ref "U2") (pin "3") (pinfunction "IN_3") (pintype "passive"))
    )
    (net (code "64") (name "VBAT_21.6V") (class "Default")
      (node (ref "D2") (pin "A") (pinfunction "A_A") (pintype "passive"))
      (node (ref "SW1") (pin "5") (pinfunction "5_5") (pintype "passive"))
    )
    (net (code "65") (name "VDD5") (class "Default")
      (node (ref "C5") (pin "1") (pinfunction "1_1") (pintype "passive"))
      (node (ref "D4") (pin "2") (pinfunction "K_2") (pintype "passive"))
      (node (ref "J1") (pin "1") (pinfunction "1_1") (pintype "passive"))
      (node (ref "R32") (pin "2") (pinfunction "2_2") (pintype "passive"))
      (node (ref "R34") (pin "1") (pinfunction "1_1") (pintype "passive"))
      (node (ref "R53") (pin "1") (pinfunction "1_1") (pintype "passive"))
      (node (ref "SW1") (pin "1") (pinfunction "1_1") (pintype "passive"))
      (node (ref "U1") (pin "10") (pinfunction "VDD5_10") (pintype "passive"))
    )
    (net (code "66") (name "unconnected-(SW1-Pad7)") (class "Default")
      (node (ref "SW1") (pin "7") (pinfunction "7_7") (pintype "passive"))
    )
    (net (code "67") (name "unconnected-(U1-P1.5{slash}C0M{slash}C2PS{slash}C5M{slash}A3P{slash}AD13{slash}DA2-Pad17)") (class "Default")
      (node (ref "U1") (pin "17") (pinfunction "P1.5/C0M/C2PS/C5M/A3P/AD13/DA2_17") (pintype "passive+no_connect"))
    )
    (net (code "68") (name "unconnected-(U1-P1.7{slash}CM1M{slash}AP1M-Pad19)") (class "Default")
      (node (ref "U1") (pin "19") (pinfunction "P1.7/CM1M/AP1M_19") (pintype "passive+no_connect"))
    )
    (net (code "69") (name "unconnected-(U1-P2.2{slash}CMP2M{slash}AMP2M-Pad21)") (class "Default")
      (node (ref "U1") (pin "21") (pinfunction "P2.2/CMP2M/AMP2M_21") (pintype "passive+no_connect"))
    )
    (net (code "70") (name "unconnected-(U1-P3.3{slash}AD6-Pad27)") (class "Default")
      (node (ref "U1") (pin "27") (pinfunction "P3.3/AD6_27") (pintype "passive"))
    )
    (net (code "71") (name "unconnected-(U1-P3.6{slash}HALL2{slash}RXD2-Pad30)") (class "Default")
      (node (ref "U1") (pin "30") (pinfunction "P3.6/HALL2/RXD2_30") (pintype "passive+no_connect"))
    )
    (net (code "72") (name "unconnected-(U1-P4.5-Pad13)") (class "Default")
      (node (ref "U1") (pin "13") (pinfunction "P4.5_13") (pintype "passive+no_connect"))
    )
  )
)
